# arduino_nano.net
KiCad netlist of a schematic drawn in Altium Designer
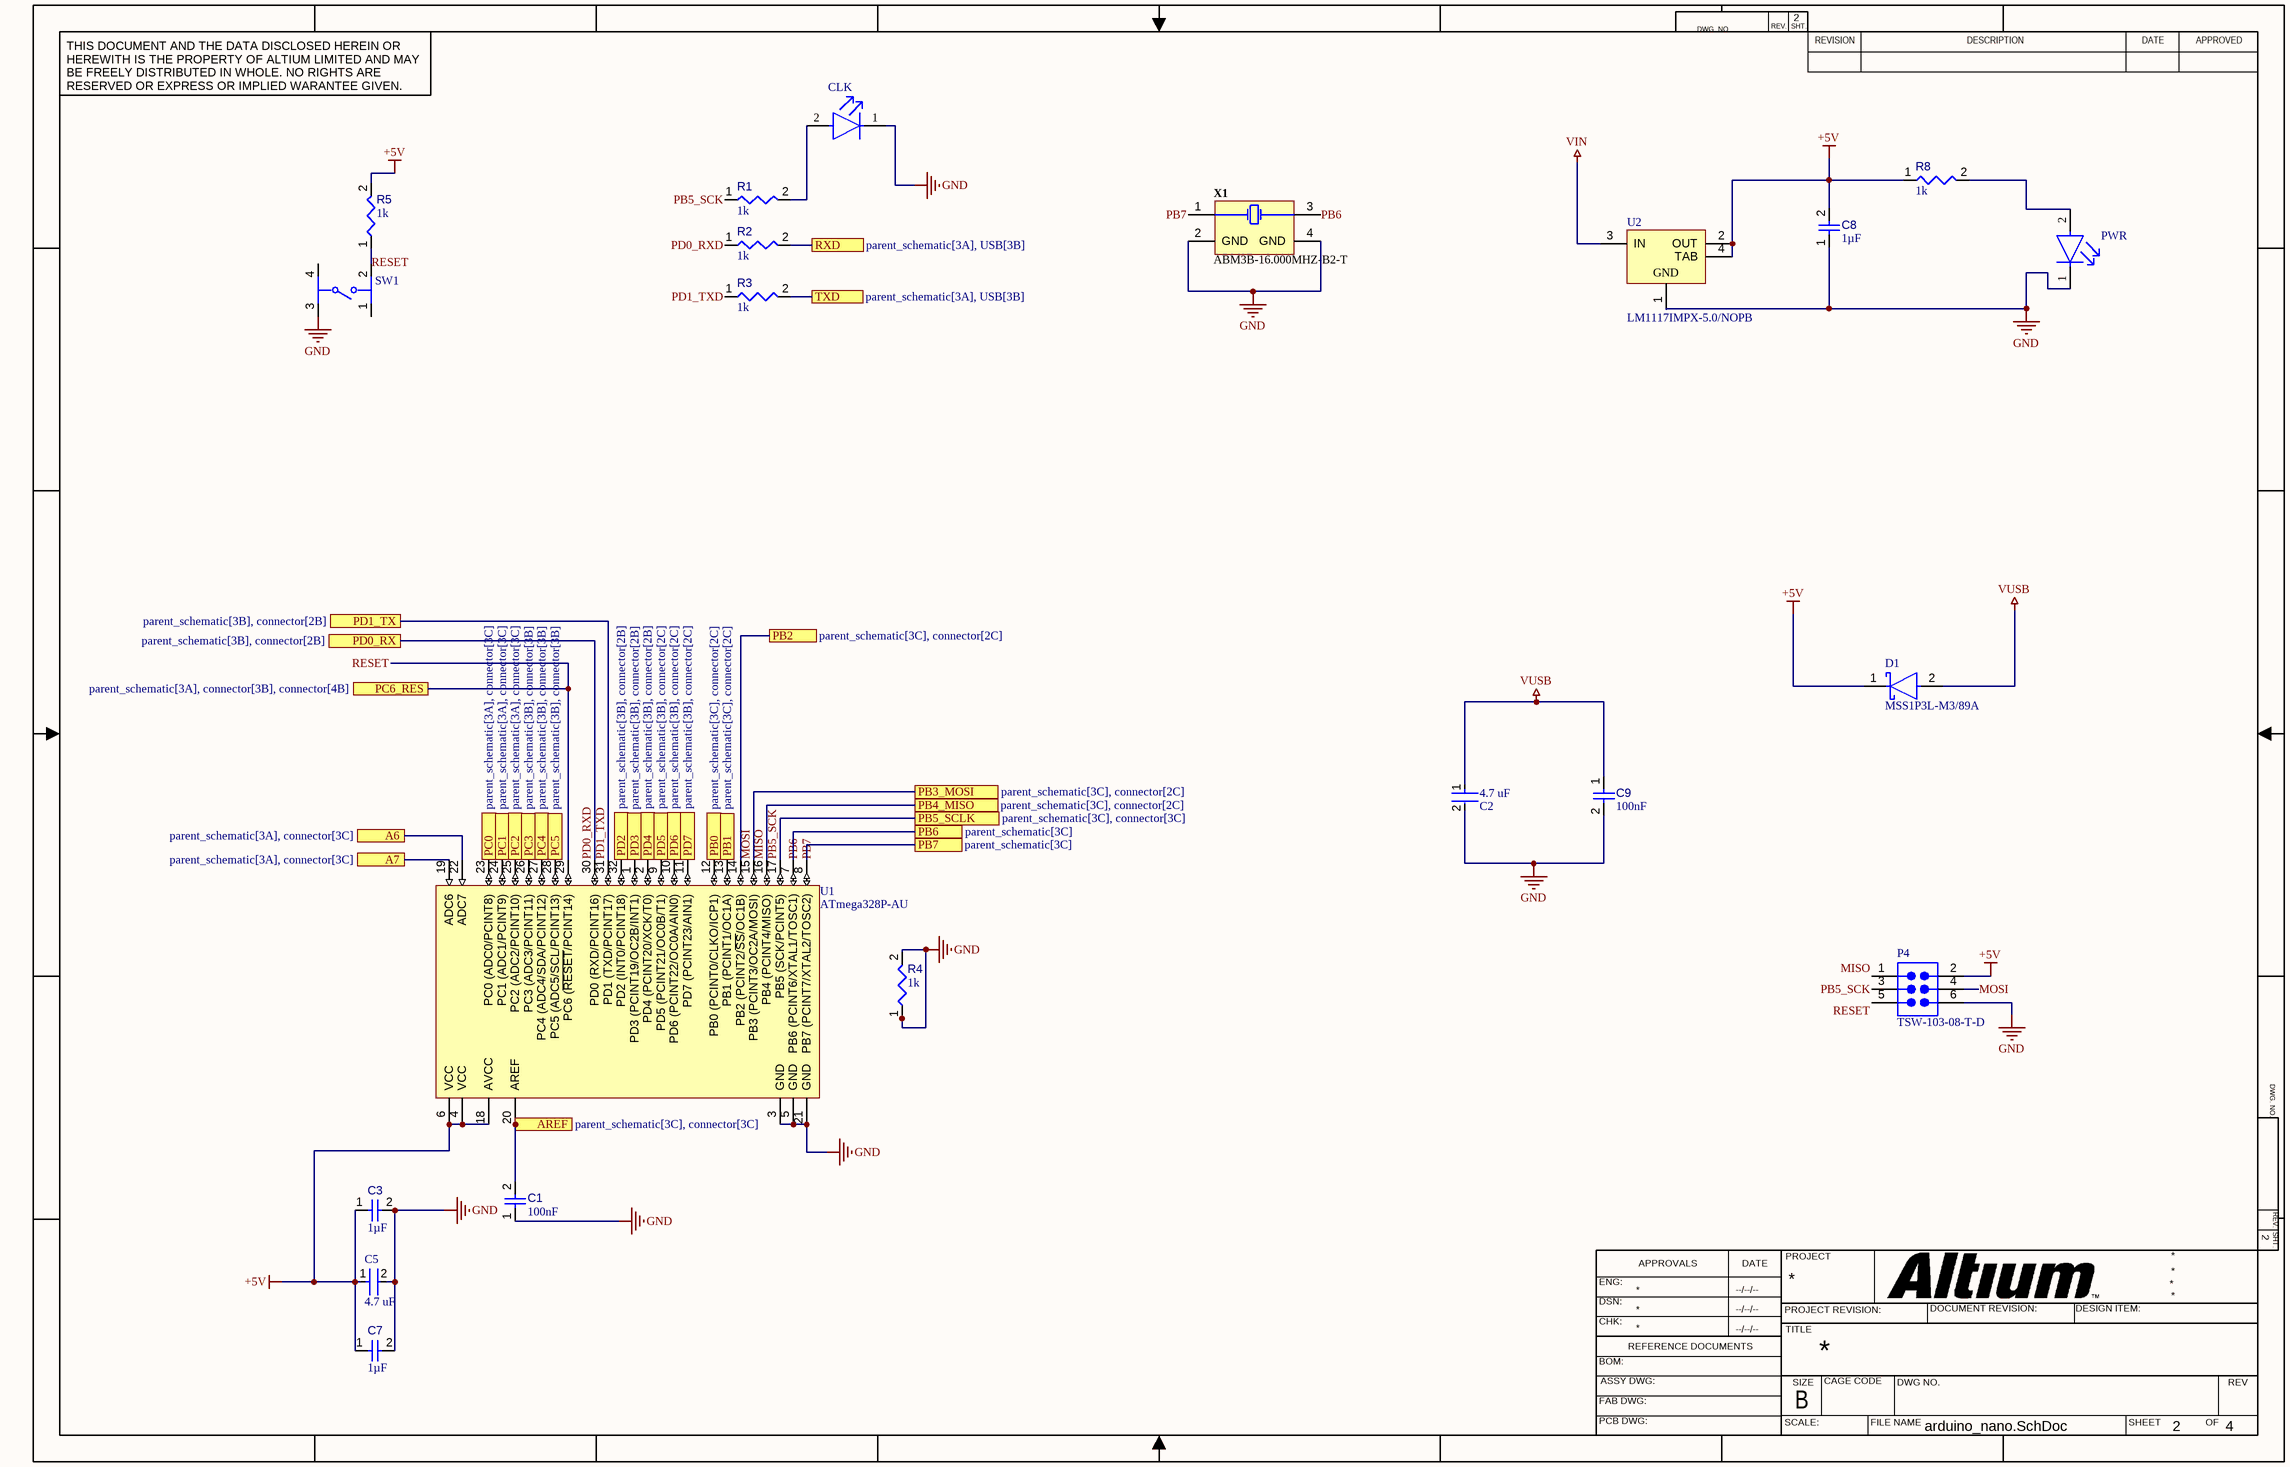
[diagram p0: arduino_nano.SchDoc]

(export (version "E")
  (design (tool "Eeschema 10.0.6"))
  (components
    (comp (ref "C1")
      (value "100nF")
      (footprint "CAPC0402(1005)60_L")
      (description "Chip Capacitor, 100nF +/-20%, 25V, 0402, Thickness 0.6 mm")
      (fields (field (name "TOLERANCE") "10%") (field (name "Comment") "Capacitor 100nF +/-20% 25V 0402"))
      (libsource (lib "Widha Rizqika Prasetya") (part "CAP-NP-2"))
    )
    (comp (ref "C2")
      (value "4.7 uF")
      (footprint "FP-GRM21B-0_15-IPC_A")
      (description "Chip Multilayer Ceramic Capacitors for General Purpose, 0805, 4.7uF, X6S, 22%, 20%, 35V")
      (fields (field (name "TOLERANCE") "20%"))
      (libsource (lib "Altium Content Vault") (part "b4654b650e69147ec39a6b967a45e02"))
    )
    (comp (ref "C3")
      (value "1µF")
      (footprint "CAPC1608X90X35ML15T15")
      (description "Chip Capacitor, 1 uF, +/- 10%, 16 V, 0603 (1608 Metric)")
      (fields (field (name "TOLERANCE") "10%") (field (name "Comment") "Capacitor 1uF +/- 10% 16V 0603"))
      (libsource (lib "Widha Rizqika Prasetya") (part "CAP-NP-2"))
    )
    (comp (ref "C5")
      (value "4.7 uF")
      (footprint "FP-GRM21B-0_15-IPC_A")
      (description "Chip Multilayer Ceramic Capacitors for General Purpose, 0805, 4.7uF, X6S, 22%, 20%, 35V")
      (fields (field (name "TOLERANCE") "20%"))
      (libsource (lib "Altium Content Vault") (part "b4654b650e69147ec39a6b967a45e02"))
    )
    (comp (ref "C7")
      (value "1µF")
      (footprint "CAPC1608X90X35ML15T15")
      (description "Chip Capacitor, 1 uF, +/- 10%, 16 V, 0603 (1608 Metric)")
      (fields (field (name "TOLERANCE") "10%") (field (name "Comment") "Capacitor 1uF +/- 10% 16V 0603"))
      (libsource (lib "Widha Rizqika Prasetya") (part "CAP-NP-2"))
    )
    (comp (ref "C8")
      (value "1µF")
      (footprint "CAPC1608X90X35ML15T15")
      (description "Chip Capacitor, 1 uF, +/- 10%, 16 V, 0603 (1608 Metric)")
      (fields (field (name "TOLERANCE") "10%") (field (name "Comment") "Capacitor 1uF +/- 10% 16V 0603"))
      (libsource (lib "Widha Rizqika Prasetya") (part "CAP-NP-2"))
    )
    (comp (ref "C9")
      (value "100nF")
      (footprint "CAPC0402(1005)60_L")
      (description "Chip Capacitor, 100nF +/-20%, 25V, 0402, Thickness 0.6 mm")
      (fields (field (name "TOLERANCE") "10%") (field (name "Comment") "Capacitor 100nF +/-20% 25V 0402"))
      (libsource (lib "Widha Rizqika Prasetya") (part "CAP-NP-2"))
    )
    (comp (ref "CLK")
      (value "~")
      (footprint "FP-5973901831F-MFG")
      (description "LED COOL WHITE 2SMD")
      (libsource (lib "Altium Content Vault") (part "8706943c75ba83719d021d2fdc84c58"))
    )
    (comp (ref "D1")
      (value "MSS1P3L-M3/89A")
      (footprint "FP-96591-MFG")
      (description "DIODE SCHOTTKY 30V 1A MICROSMP")
      (fields
        (field (name "OCTOPART") "https://octopart.com/mss1p3l-m3%2F89a-vishay-42670898")
        (field (name "MANUFACTURER") "Vishay")
      )
      (libsource (lib "Altium Content Vault") (part "1d6ec82d83fb6aee721767c19dac4b9"))
    )
    (comp (ref "P4")
      (value "TSW-103-08-T-D")
      (footprint "SMTC-TSW-103-08-X-D")
      (description "0.025\" SQ Post Header, Through-hole, Vertical, -55 to 105 degC, 2.54 mm Pitch, 6-Pin, Male, RoHS")
      (fields (field (name "MANUFACTURER") "Samtec"))
      (libsource (lib "Altium Content Vault") (part "SMTC-TSW-103-08-X-D"))
    )
    (comp (ref "PWR")
      (value "~")
      (footprint "FP-5973901831F-MFG")
      (description "LED COOL WHITE 2SMD")
      (libsource (lib "Altium Content Vault") (part "8706943c75ba83719d021d2fdc84c58"))
    )
    (comp (ref "R1")
      (value "1k")
      (footprint "RESC2012X70N")
      (description "Res Thick Film 0805 1K Ohm 5% 0.5W(1/2W) ±200ppm/C Pad SMD Automotive T/R")
      (fields (field (name "TOLERANCE") "5%") (field (name "Comment") "ERJP06J102V_with_model"))
      (libsource (lib "Widha Rizqika Prasetya") (part "RES-2"))
    )
    (comp (ref "R2")
      (value "1k")
      (footprint "RESC2012X70N")
      (description "Res Thick Film 0805 1K Ohm 5% 0.5W(1/2W) ±200ppm/C Pad SMD Automotive T/R")
      (fields (field (name "TOLERANCE") "5%") (field (name "Comment") "ERJP06J102V_with_model"))
      (libsource (lib "Widha Rizqika Prasetya") (part "RES-2"))
    )
    (comp (ref "R3")
      (value "1k")
      (footprint "RESC2012X70N")
      (description "Res Thick Film 0805 1K Ohm 5% 0.5W(1/2W) ±200ppm/C Pad SMD Automotive T/R")
      (fields (field (name "TOLERANCE") "5%") (field (name "Comment") "ERJP06J102V_with_model"))
      (libsource (lib "Widha Rizqika Prasetya") (part "RES-2"))
    )
    (comp (ref "R4")
      (value "1k")
      (footprint "RESC2012X70N")
      (description "Res Thick Film 0805 1K Ohm 5% 0.5W(1/2W) ±200ppm/C Pad SMD Automotive T/R")
      (fields (field (name "TOLERANCE") "5%") (field (name "Comment") "ERJP06J102V_with_model"))
      (libsource (lib "Widha Rizqika Prasetya") (part "RES-2"))
    )
    (comp (ref "R5")
      (value "1k")
      (footprint "RESC2012X70N")
      (description "Res Thick Film 0805 1K Ohm 5% 0.5W(1/2W) ±200ppm/C Pad SMD Automotive T/R")
      (fields (field (name "TOLERANCE") "5%") (field (name "Comment") "ERJP06J102V_with_model"))
      (libsource (lib "Widha Rizqika Prasetya") (part "RES-2"))
    )
    (comp (ref "R8")
      (value "1k")
      (footprint "RESC2012X70N")
      (description "Res Thick Film 0805 1K Ohm 5% 0.5W(1/2W) ±200ppm/C Pad SMD Automotive T/R")
      (fields (field (name "TOLERANCE") "5%") (field (name "Comment") "ERJP06J102V_with_model"))
      (libsource (lib "Widha Rizqika Prasetya") (part "RES-2"))
    )
    (comp (ref "SW1")
      (value "~")
      (footprint "FP-PTS810SJM250SMTRLFS-MFG")
      (description "SWITCH TACTILE SPST-NO 0.05A 16V")
      (libsource (lib "Altium Content Vault") (part "1adf0dd01260c80cf25a44bfd6b99ba"))
    )
    (comp (ref "U1")
      (value "ATmega328P-AU")
      (footprint "32A_M")
      (libsource (lib "Altium Content Vault") (part "MC-8B-ATM48-SQ32"))
    )
    (comp (ref "U2")
      (value "LM1117IMPX-5.0/NOPB")
      (footprint "MP04A_M")
      (description "800mA Low-Dropout Linear Regulator, 4-pin SOT-223, Pb-Free")
      (fields (field (name "MANUFACTURER") "National Semiconductor"))
      (libsource (lib "Altium Content Vault") (part "PM-REG-LM1086-SOT4"))
    )
    (comp (ref "X1")
      (value "ABM3B-16.000MHZ-B2-T")
      (footprint "ABRA-ABM3B-4_V")
      (description "Ceramic SMD Crystal, 16 MHz, +/- 20 ppm, 18 pF, -20 to 70 degC, 4-Pin SMD, RoHS, Tape and Reel")
      (fields (field (name "TOLERANCE") "20ppm") (field (name "MANUFACTURER") "Abracon"))
      (libsource (lib "Widha Rizqika Prasetya") (part "XTAL-1-3-4"))
    )
  )
  (nets
    (net (code "1") (name "+5V") (class "Default")
      (node (ref "C3") (pin "1") (pinfunction "1_1") (pintype "passive"))
      (node (ref "C5") (pin "1") (pinfunction "1_1") (pintype "passive"))
      (node (ref "C7") (pin "1") (pinfunction "1_1") (pintype "passive"))
      (node (ref "C8") (pin "2") (pinfunction "2_2") (pintype "passive"))
      (node (ref "D1") (pin "1") (pinfunction "C_1") (pintype "passive"))
      (node (ref "P4") (pin "2") (pinfunction "2_2") (pintype "passive"))
      (node (ref "R5") (pin "2") (pinfunction "2_2") (pintype "passive"))
      (node (ref "R8") (pin "1") (pinfunction "1_1") (pintype "passive"))
      (node (ref "U1") (pin "18") (pinfunction "AVCC_18") (pintype "power_in"))
      (node (ref "U1") (pin "4") (pinfunction "VCC_4") (pintype "power_in"))
      (node (ref "U1") (pin "6") (pinfunction "VCC_6") (pintype "power_in"))
      (node (ref "U2") (pin "2") (pinfunction "OUT_2") (pintype "power_in"))
      (node (ref "U2") (pin "4") (pinfunction "TAB_4") (pintype "power_in"))
    )
    (net (code "2") (name "/A6") (class "Default")
      (node (ref "U1") (pin "22") (pinfunction "ADC7_22") (pintype "input"))
    )
    (net (code "3") (name "/A7") (class "Default")
      (node (ref "U1") (pin "19") (pinfunction "ADC6_19") (pintype "input"))
    )
    (net (code "4") (name "/AREF") (class "Default")
      (node (ref "C1") (pin "2") (pinfunction "2_2") (pintype "passive"))
      (node (ref "U1") (pin "20") (pinfunction "AREF_20") (pintype "passive"))
    )
    (net (code "5") (name "/MISO") (class "Default")
      (node (ref "P4") (pin "1") (pinfunction "1_1") (pintype "passive"))
      (node (ref "U1") (pin "16") (pinfunction "PB4_(PCINT4/MISO)_16") (pintype "bidirectional"))
    )
    (net (code "6") (name "/MOSI") (class "Default")
      (node (ref "P4") (pin "4") (pinfunction "4_4") (pintype "passive"))
      (node (ref "U1") (pin "15") (pinfunction "PB3_(PCINT3/OC2A/MOSI)_15") (pintype "bidirectional"))
    )
    (net (code "7") (name "/PB0") (class "Default")
      (node (ref "U1") (pin "12") (pinfunction "PB0_(PCINT0/CLKO/ICP1)_12") (pintype "bidirectional"))
    )
    (net (code "8") (name "/PB1") (class "Default")
      (node (ref "U1") (pin "13") (pinfunction "PB1_(PCINT1/OC1A)_13") (pintype "bidirectional"))
    )
    (net (code "9") (name "/PB2") (class "Default")
      (node (ref "U1") (pin "14") (pinfunction "PB2_(PCINT2/~{SS}/OC1B)_14") (pintype "bidirectional"))
    )
    (net (code "10") (name "/PB5_SCK") (class "Default")
      (node (ref "P4") (pin "3") (pinfunction "3_3") (pintype "passive"))
      (node (ref "R1") (pin "1") (pinfunction "1_1") (pintype "passive"))
      (node (ref "U1") (pin "17") (pinfunction "PB5_(SCK/PCINT5)_17") (pintype "bidirectional"))
    )
    (net (code "11") (name "/PB6") (class "Default")
      (node (ref "U1") (pin "7") (pinfunction "PB6_(PCINT6/XTAL1/TOSC1)_7") (pintype "bidirectional"))
      (node (ref "X1") (pin "3") (pinfunction "X2_3") (pintype "passive"))
    )
    (net (code "12") (name "/PB7") (class "Default")
      (node (ref "U1") (pin "8") (pinfunction "PB7_(PCINT7/XTAL2/TOSC2)_8") (pintype "bidirectional"))
      (node (ref "X1") (pin "1") (pinfunction "X1_1") (pintype "passive"))
    )
    (net (code "13") (name "/PC0") (class "Default")
      (node (ref "U1") (pin "23") (pinfunction "PC0_(ADC0/PCINT8)_23") (pintype "bidirectional"))
    )
    (net (code "14") (name "/PC1") (class "Default")
      (node (ref "U1") (pin "24") (pinfunction "PC1_(ADC1/PCINT9)_24") (pintype "bidirectional"))
    )
    (net (code "15") (name "/PC2") (class "Default")
      (node (ref "U1") (pin "25") (pinfunction "PC2_(ADC2/PCINT10)_25") (pintype "bidirectional"))
    )
    (net (code "16") (name "/PC3") (class "Default")
      (node (ref "U1") (pin "26") (pinfunction "PC3_(ADC3/PCINT11)_26") (pintype "bidirectional"))
    )
    (net (code "17") (name "/PC4") (class "Default")
      (node (ref "U1") (pin "27") (pinfunction "PC4_(ADC4/SDA/PCINT12)_27") (pintype "bidirectional"))
    )
    (net (code "18") (name "/PC5") (class "Default")
      (node (ref "U1") (pin "28") (pinfunction "PC5_(ADC5/SCL/PCINT13)_28") (pintype "bidirectional"))
    )
    (net (code "19") (name "/PD0_RXD") (class "Default")
      (node (ref "R2") (pin "1") (pinfunction "1_1") (pintype "passive"))
      (node (ref "U1") (pin "30") (pinfunction "PD0_(RXD/PCINT16)_30") (pintype "bidirectional"))
    )
    (net (code "20") (name "/PD1_TXD") (class "Default")
      (node (ref "R3") (pin "1") (pinfunction "1_1") (pintype "passive"))
      (node (ref "U1") (pin "31") (pinfunction "PD1_(TXD/PCINT17)_31") (pintype "bidirectional"))
    )
    (net (code "21") (name "/PD2") (class "Default")
      (node (ref "U1") (pin "32") (pinfunction "PD2_(INT0/PCINT18)_32") (pintype "bidirectional"))
    )
    (net (code "22") (name "/PD3") (class "Default")
      (node (ref "U1") (pin "1") (pinfunction "PD3_(PCINT19/OC2B/INT1)_1") (pintype "bidirectional"))
    )
    (net (code "23") (name "/PD4") (class "Default")
      (node (ref "U1") (pin "2") (pinfunction "PD4_(PCINT20/XCK/T0)_2") (pintype "bidirectional"))
    )
    (net (code "24") (name "/PD5") (class "Default")
      (node (ref "U1") (pin "9") (pinfunction "PD5_(PCINT21/OC0B/T1)_9") (pintype "bidirectional"))
    )
    (net (code "25") (name "/PD6") (class "Default")
      (node (ref "U1") (pin "10") (pinfunction "PD6_(PCINT22/OC0A/AIN0)_10") (pintype "bidirectional"))
    )
    (net (code "26") (name "/PD7") (class "Default")
      (node (ref "U1") (pin "11") (pinfunction "PD7_(PCINT23/AIN1)_11") (pintype "bidirectional"))
    )
    (net (code "27") (name "/RESET") (class "Default")
      (node (ref "P4") (pin "5") (pinfunction "5_5") (pintype "passive"))
      (node (ref "R5") (pin "1") (pinfunction "1_1") (pintype "passive"))
      (node (ref "SW1") (pin "2") (pinfunction "2_2") (pintype "passive"))
      (node (ref "U1") (pin "29") (pinfunction "PC6_(~{RESET}/PCINT14)_29") (pintype "bidirectional"))
    )
    (net (code "28") (name "/RXD") (class "Default")
      (node (ref "R2") (pin "2") (pinfunction "2_2") (pintype "passive"))
    )
    (net (code "29") (name "/TXD") (class "Default")
      (node (ref "R3") (pin "2") (pinfunction "2_2") (pintype "passive"))
    )
    (net (code "30") (name "GND") (class "Default")
      (node (ref "C1") (pin "1") (pinfunction "1_1") (pintype "passive"))
      (node (ref "C2") (pin "2") (pinfunction "2_2") (pintype "passive"))
      (node (ref "C3") (pin "2") (pinfunction "2_2") (pintype "passive"))
      (node (ref "C5") (pin "2") (pinfunction "2_2") (pintype "passive"))
      (node (ref "C7") (pin "2") (pinfunction "2_2") (pintype "passive"))
      (node (ref "C8") (pin "1") (pinfunction "1_1") (pintype "passive"))
      (node (ref "C9") (pin "2") (pinfunction "2_2") (pintype "passive"))
      (node (ref "CLK") (pin "1") (pinfunction "C_1") (pintype "passive"))
      (node (ref "P4") (pin "6") (pinfunction "6_6") (pintype "passive"))
      (node (ref "PWR") (pin "1") (pinfunction "C_1") (pintype "passive"))
      (node (ref "R4") (pin "1") (pinfunction "1_1") (pintype "passive"))
      (node (ref "SW1") (pin "3") (pinfunction "3_3") (pintype "passive"))
      (node (ref "U1") (pin "21") (pinfunction "GND_21") (pintype "power_in"))
      (node (ref "U1") (pin "3") (pinfunction "GND_3") (pintype "power_in"))
      (node (ref "U1") (pin "5") (pinfunction "GND_5") (pintype "power_in"))
      (node (ref "U2") (pin "1") (pinfunction "GND_1") (pintype "power_in"))
      (node (ref "X1") (pin "2") (pinfunction "GND_2") (pintype "power_in"))
      (node (ref "X1") (pin "4") (pinfunction "GND_4") (pintype "power_in"))
    )
    (net (code "31") (name "Net-(CLK-A)") (class "Default")
      (node (ref "CLK") (pin "2") (pinfunction "A_2") (pintype "passive"))
      (node (ref "R1") (pin "2") (pinfunction "2_2") (pintype "passive"))
    )
    (net (code "32") (name "Net-(PWR-A)") (class "Default")
      (node (ref "PWR") (pin "2") (pinfunction "A_2") (pintype "passive"))
      (node (ref "R8") (pin "2") (pinfunction "2_2") (pintype "passive"))
    )
    (net (code "33") (name "VIN") (class "Default")
      (node (ref "U2") (pin "3") (pinfunction "IN_3") (pintype "power_in"))
    )
    (net (code "34") (name "VUSB") (class "Default")
      (node (ref "C2") (pin "1") (pinfunction "1_1") (pintype "passive"))
      (node (ref "C9") (pin "1") (pinfunction "1_1") (pintype "passive"))
      (node (ref "D1") (pin "2") (pinfunction "A_2") (pintype "passive"))
    )
    (net (code "35") (name "unconnected-(R4-Pad2)") (class "Default")
      (node (ref "R4") (pin "2") (pinfunction "2_2") (pintype "passive"))
    )
    (net (code "36") (name "unconnected-(SW1-Pad1)") (class "Default")
      (node (ref "SW1") (pin "1") (pinfunction "1_1") (pintype "passive"))
    )
    (net (code "37") (name "unconnected-(SW1-Pad4)") (class "Default")
      (node (ref "SW1") (pin "4") (pinfunction "4_4") (pintype "passive"))
    )
  )
)
